# 00A-100.net
KiCad netlist of a schematic drawn in EAGLE
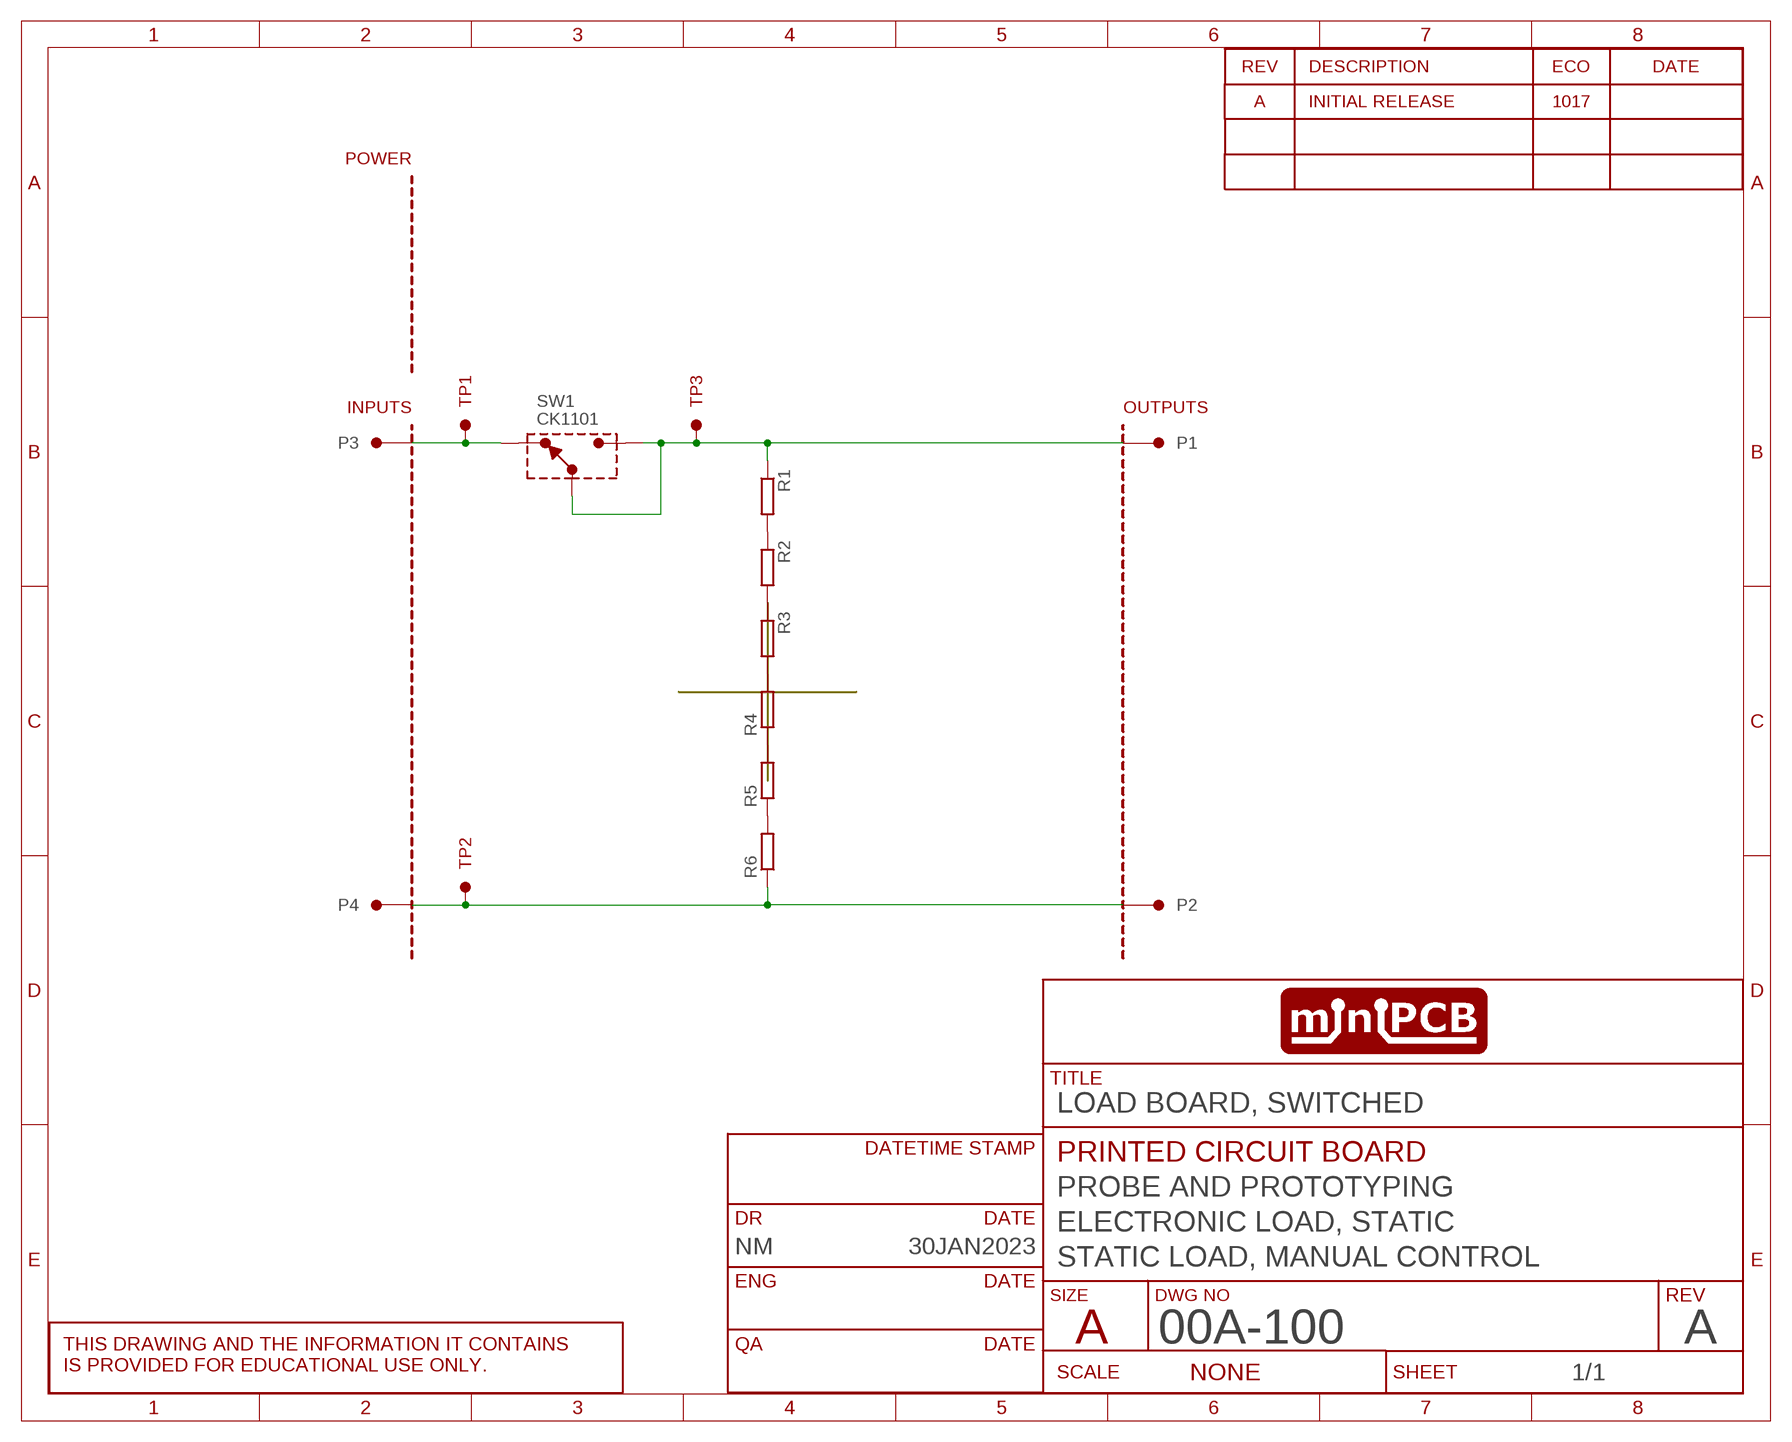
[diagram p0: schematic, sheet 1]

(export (version "E")
  (design (tool "Eeschema 10.0.6"))
  (components
    (comp (ref "P1")
      (value "PINS_1KE6060")
      (footprint "eagle-import:PINS_1_KE6060")
      (libsource (lib "eagle-import") (part "PINS_1KE6060"))
    )
    (comp (ref "P2")
      (value "PINS_1KE6060")
      (footprint "eagle-import:PINS_1_KE6060")
      (libsource (lib "eagle-import") (part "PINS_1KE6060"))
    )
    (comp (ref "P3")
      (value "PINS_15699-0")
      (footprint "eagle-import:BANANAPOST")
      (libsource (lib "eagle-import") (part "PINS_15699-0"))
    )
    (comp (ref "P4")
      (value "PINS_15699-0")
      (footprint "eagle-import:BANANAPOST")
      (libsource (lib "eagle-import") (part "PINS_15699-0"))
    )
    (comp (ref "PCB1")
      (value "MINIPCB_0P50X50")
      (footprint "eagle-import:MINIPCB_0P_50X50MM")
      (fields (field (name "PART_NUMBER") "00A-100-A"))
      (libsource (lib "eagle-import") (part "MINIPCB_0P50X50"))
    )
    (comp (ref "R1")
      (value "RESISTOR15MM")
      (footprint "eagle-import:R-THD-15MM")
      (libsource (lib "eagle-import") (part "RESISTOR15MM"))
    )
    (comp (ref "R2")
      (value "RESISTOR15MM")
      (footprint "eagle-import:R-THD-15MM")
      (libsource (lib "eagle-import") (part "RESISTOR15MM"))
    )
    (comp (ref "R3")
      (value "RESISTOR15MM")
      (footprint "eagle-import:R-THD-15MM")
      (libsource (lib "eagle-import") (part "RESISTOR15MM"))
    )
    (comp (ref "R4")
      (value "RESISTOR15MM")
      (footprint "eagle-import:R-THD-15MM")
      (libsource (lib "eagle-import") (part "RESISTOR15MM"))
    )
    (comp (ref "R5")
      (value "RESISTOR15MM")
      (footprint "eagle-import:R-THD-15MM")
      (libsource (lib "eagle-import") (part "RESISTOR15MM"))
    )
    (comp (ref "R6")
      (value "RESISTOR15MM")
      (footprint "eagle-import:R-THD-15MM")
      (libsource (lib "eagle-import") (part "RESISTOR15MM"))
    )
    (comp (ref "SW1")
      (value "CK1101")
      (footprint "eagle-import:CK1101")
      (libsource (lib "eagle-import") (part "SPDTM2S3CQE2"))
    )
    (comp (ref "TP1")
      (value "TESTPOINTKE5100")
      (footprint "eagle-import:PINS_1_TESTPOINT_KE5100")
      (libsource (lib "eagle-import") (part "TESTPOINTKE5100"))
    )
    (comp (ref "TP2")
      (value "TESTPOINTKE5100")
      (footprint "eagle-import:PINS_1_TESTPOINT_KE5100")
      (libsource (lib "eagle-import") (part "TESTPOINTKE5100"))
    )
    (comp (ref "TP3")
      (value "TESTPOINTKE5100")
      (footprint "eagle-import:PINS_1_TESTPOINT_KE5100")
      (libsource (lib "eagle-import") (part "TESTPOINTKE5100"))
    )
  )
  (nets
    (net (code "1") (name "Net-(P2-1-Pad2)") (class "Default")
      (node (ref "P2") (pin "1") (pinfunction "1_1") (pintype "bidirectional"))
      (node (ref "P2") (pin "2") (pinfunction "1_2") (pintype "bidirectional"))
      (node (ref "P4") (pin "1") (pinfunction "1_1") (pintype "bidirectional"))
      (node (ref "R6") (pin "1") (pinfunction "1_1") (pintype "passive"))
      (node (ref "TP2") (pin "1") (pinfunction "1_1") (pintype "bidirectional"))
    )
    (net (code "2") (name "Net-(R1-Pad2)") (class "Default")
      (node (ref "R1") (pin "2") (pinfunction "2_2") (pintype "passive"))
      (node (ref "R2") (pin "1") (pinfunction "1_1") (pintype "passive"))
    )
    (net (code "3") (name "Net-(R2-Pad2)") (class "Default")
      (node (ref "R2") (pin "2") (pinfunction "2_2") (pintype "passive"))
      (node (ref "R3") (pin "1") (pinfunction "1_1") (pintype "passive"))
    )
    (net (code "4") (name "Net-(R3-Pad2)") (class "Default")
      (node (ref "R3") (pin "2") (pinfunction "2_2") (pintype "passive"))
      (node (ref "R4") (pin "2") (pinfunction "2_2") (pintype "passive"))
    )
    (net (code "5") (name "Net-(R4-Pad1)") (class "Default")
      (node (ref "R4") (pin "1") (pinfunction "1_1") (pintype "passive"))
      (node (ref "R5") (pin "2") (pinfunction "2_2") (pintype "passive"))
    )
    (net (code "6") (name "Net-(R5-Pad1)") (class "Default")
      (node (ref "R5") (pin "1") (pinfunction "1_1") (pintype "passive"))
      (node (ref "R6") (pin "2") (pinfunction "2_2") (pintype "passive"))
    )
    (net (code "7") (name "Net-(SW1-1)") (class "Default")
      (node (ref "P3") (pin "1") (pinfunction "1_1") (pintype "bidirectional"))
      (node (ref "SW1") (pin "P$1") (pinfunction "1_P$1") (pintype "bidirectional"))
      (node (ref "TP1") (pin "1") (pinfunction "1_1") (pintype "bidirectional"))
    )
    (net (code "8") (name "Net-(SW1-2)") (class "Default")
      (node (ref "P1") (pin "1") (pinfunction "1_1") (pintype "bidirectional"))
      (node (ref "P1") (pin "2") (pinfunction "1_2") (pintype "bidirectional"))
      (node (ref "R1") (pin "1") (pinfunction "1_1") (pintype "passive"))
      (node (ref "SW1") (pin "P$2") (pinfunction "2_P$2") (pintype "bidirectional"))
      (node (ref "SW1") (pin "P$3") (pinfunction "3_P$3") (pintype "bidirectional"))
      (node (ref "TP3") (pin "1") (pinfunction "1_1") (pintype "bidirectional"))
    )
  )
)
